# IR_Sync_Emitter.net
KiCad netlist of a schematic drawn in EAGLE
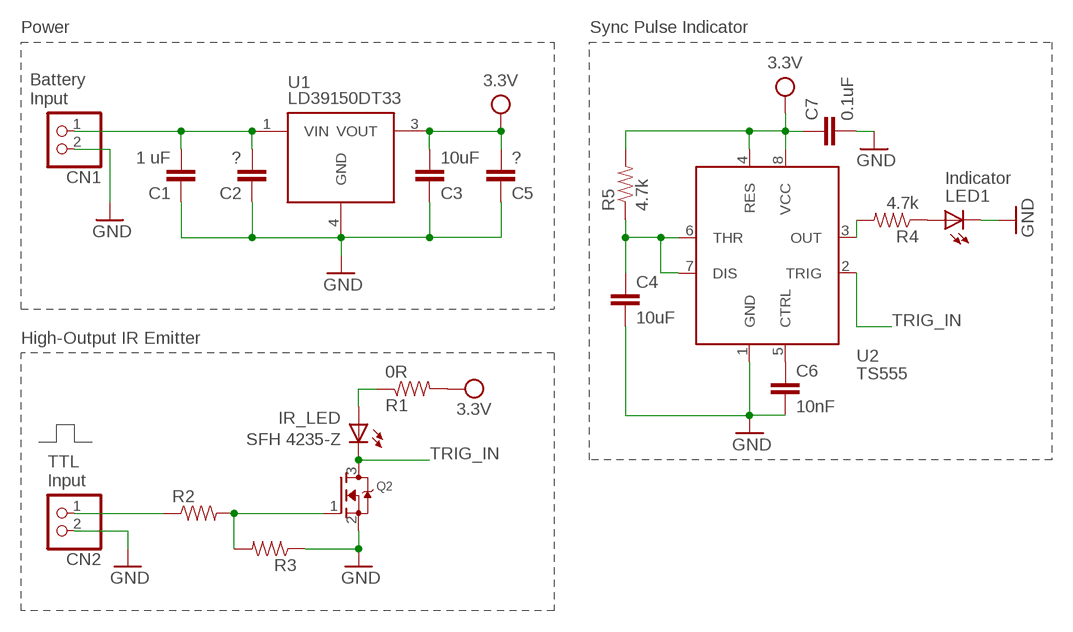
[diagram p0: schematic, sheet 1]

(export (version "E")
  (design (tool "Eeschema 10.0.6"))
  (components
    (comp (ref "C1")
      (value "1 uF")
      (footprint "eagle-import:CAPC2012X100N")
      (libsource (lib "eagle-import") (part "CC0805-N"))
    )
    (comp (ref "C2")
      (value "?")
      (footprint "eagle-import:CAPC2012X100N")
      (libsource (lib "eagle-import") (part "CC0805-N"))
    )
    (comp (ref "C3")
      (value "10uF")
      (footprint "eagle-import:CAPC2012X100N")
      (libsource (lib "eagle-import") (part "CC0805-N"))
    )
    (comp (ref "C4")
      (value "10uF")
      (footprint "eagle-import:CAPC2012X100N")
      (libsource (lib "eagle-import") (part "CC0805-N"))
    )
    (comp (ref "C5")
      (value "?")
      (footprint "eagle-import:CAPC2012X100N")
      (libsource (lib "eagle-import") (part "CC0805-N"))
    )
    (comp (ref "C6")
      (value "10nF")
      (footprint "eagle-import:CAPC2012X100N")
      (libsource (lib "eagle-import") (part "CC0805-N"))
    )
    (comp (ref "C7")
      (value "0.1uF")
      (footprint "eagle-import:CAPC2012X100N")
      (libsource (lib "eagle-import") (part "CC0805-N"))
    )
    (comp (ref "CN1")
      (value "JST_2PIN-SMT-RA")
      (footprint "eagle-import:JST-PH-2-SMT-RA")
      (libsource (lib "eagle-import") (part "JST_2PIN-SMT-RA"))
    )
    (comp (ref "CN2")
      (value "JST_2PIN-SMT-RA")
      (footprint "eagle-import:JST-PH-2-SMT-RA")
      (libsource (lib "eagle-import") (part "JST_2PIN-SMT-RA"))
    )
    (comp (ref "IR_LED")
      (value "LEDIR_SMT16.2X11.2")
      (footprint "eagle-import:LED_SMT6.2X11.2")
      (libsource (lib "eagle-import") (part "LEDIR_SMT16.2X11.2"))
    )
    (comp (ref "LED1")
      (value "LED0603")
      (footprint "eagle-import:CHIPLED_0603")
      (libsource (lib "eagle-import") (part "LED0603"))
    )
    (comp (ref "Q2")
      (value "MOSFET-NREFLOW")
      (footprint "eagle-import:SOT23")
      (libsource (lib "eagle-import") (part "MOSFET-NREFLOW"))
    )
    (comp (ref "R1")
      (value "0R")
      (footprint "eagle-import:RESC3116X65N")
      (libsource (lib "eagle-import") (part "RR1206-N"))
    )
    (comp (ref "R2")
      (value "RR0805-N")
      (footprint "eagle-import:RESC2012X60N")
      (libsource (lib "eagle-import") (part "RR0805-N"))
    )
    (comp (ref "R3")
      (value "RR0805-N")
      (footprint "eagle-import:RESC2012X60N")
      (libsource (lib "eagle-import") (part "RR0805-N"))
    )
    (comp (ref "R4")
      (value "4.7k")
      (footprint "eagle-import:RESC2012X60N")
      (libsource (lib "eagle-import") (part "RR0805-N"))
    )
    (comp (ref "R5")
      (value "4.7k")
      (footprint "eagle-import:RESC2012X60N")
      (libsource (lib "eagle-import") (part "RR0805-N"))
    )
    (comp (ref "U1")
      (value "LM2931_FIXED")
      (footprint "eagle-import:DPAK")
      (libsource (lib "eagle-import") (part "LM2931_FIXED"))
    )
    (comp (ref "U2")
      (value "TS555")
      (footprint "eagle-import:SO08")
      (libsource (lib "eagle-import") (part "TS555"))
    )
  )
  (nets
    (net (code "1") (name "/TRIG_IN") (class "Default")
      (node (ref "IR_LED") (pin "C") (pinfunction "C_C") (pintype "passive"))
      (node (ref "Q2") (pin "3") (pinfunction "D_3") (pintype "bidirectional"))
      (node (ref "U2") (pin "2") (pinfunction "TRIG_2") (pintype "bidirectional"))
    )
    (net (code "2") (name "GND") (class "Default")
      (node (ref "C1") (pin "1") (pinfunction "1_1") (pintype "passive"))
      (node (ref "C2") (pin "1") (pinfunction "1_1") (pintype "passive"))
      (node (ref "C3") (pin "1") (pinfunction "1_1") (pintype "passive"))
      (node (ref "C4") (pin "2") (pinfunction "2_2") (pintype "passive"))
      (node (ref "C5") (pin "1") (pinfunction "1_1") (pintype "passive"))
      (node (ref "C6") (pin "2") (pinfunction "2_2") (pintype "passive"))
      (node (ref "C7") (pin "2") (pinfunction "2_2") (pintype "passive"))
      (node (ref "CN1") (pin "2") (pinfunction "1_2") (pintype "passive"))
      (node (ref "CN2") (pin "2") (pinfunction "1_2") (pintype "passive"))
      (node (ref "LED1") (pin "C") (pinfunction "C_C") (pintype "passive"))
      (node (ref "Q2") (pin "2") (pinfunction "S_2") (pintype "bidirectional"))
      (node (ref "R3") (pin "1") (pinfunction "1_1") (pintype "passive"))
      (node (ref "U1") (pin "4") (pinfunction "GND_4") (pintype "bidirectional"))
      (node (ref "U2") (pin "1") (pinfunction "GND_1") (pintype "power_in"))
    )
    (net (code "3") (name "Net-(CN1-2)") (class "Default")
      (node (ref "C1") (pin "2") (pinfunction "2_2") (pintype "passive"))
      (node (ref "C2") (pin "2") (pinfunction "2_2") (pintype "passive"))
      (node (ref "CN1") (pin "1") (pinfunction "2_1") (pintype "passive"))
      (node (ref "U1") (pin "1") (pinfunction "VIN_1") (pintype "bidirectional"))
    )
    (net (code "4") (name "Net-(CN2-2)") (class "Default")
      (node (ref "CN2") (pin "1") (pinfunction "2_1") (pintype "passive"))
      (node (ref "R2") (pin "1") (pinfunction "1_1") (pintype "passive"))
    )
    (net (code "5") (name "Net-(IR_LED-PadA)") (class "Default")
      (node (ref "IR_LED") (pin "A") (pinfunction "A_A") (pintype "passive"))
      (node (ref "R1") (pin "1") (pinfunction "1_1") (pintype "passive"))
    )
    (net (code "6") (name "Net-(LED1-PadA)") (class "Default")
      (node (ref "LED1") (pin "A") (pinfunction "A_A") (pintype "passive"))
      (node (ref "R4") (pin "1") (pinfunction "1_1") (pintype "passive"))
    )
    (net (code "7") (name "Net-(Q2-G)") (class "Default")
      (node (ref "Q2") (pin "1") (pinfunction "G_1") (pintype "bidirectional"))
      (node (ref "R2") (pin "2") (pinfunction "2_2") (pintype "passive"))
      (node (ref "R3") (pin "2") (pinfunction "2_2") (pintype "passive"))
    )
    (net (code "8") (name "Net-(U2-CTRL)") (class "Default")
      (node (ref "C6") (pin "1") (pinfunction "1_1") (pintype "passive"))
      (node (ref "U2") (pin "5") (pinfunction "CTRL_5") (pintype "bidirectional"))
    )
    (net (code "9") (name "Net-(U2-DIS)") (class "Default")
      (node (ref "C4") (pin "1") (pinfunction "1_1") (pintype "passive"))
      (node (ref "R5") (pin "1") (pinfunction "1_1") (pintype "passive"))
      (node (ref "U2") (pin "6") (pinfunction "THR_6") (pintype "bidirectional"))
      (node (ref "U2") (pin "7") (pinfunction "DIS_7") (pintype "bidirectional"))
    )
    (net (code "10") (name "Net-(U2-OUT)") (class "Default")
      (node (ref "R4") (pin "2") (pinfunction "2_2") (pintype "passive"))
      (node (ref "U2") (pin "3") (pinfunction "OUT_3") (pintype "output"))
    )
    (net (code "11") (name "VDD") (class "Default")
      (node (ref "C3") (pin "2") (pinfunction "2_2") (pintype "passive"))
      (node (ref "C5") (pin "2") (pinfunction "2_2") (pintype "passive"))
      (node (ref "C7") (pin "1") (pinfunction "1_1") (pintype "passive"))
      (node (ref "R1") (pin "2") (pinfunction "2_2") (pintype "passive"))
      (node (ref "R5") (pin "2") (pinfunction "2_2") (pintype "passive"))
      (node (ref "U1") (pin "3") (pinfunction "VOUT_3") (pintype "bidirectional"))
      (node (ref "U2") (pin "4") (pinfunction "RES_4") (pintype "bidirectional"))
      (node (ref "U2") (pin "8") (pinfunction "VCC_8") (pintype "power_in"))
    )
  )
)
